# P07_BCS1_Exp_Conn.net
KiCad netlist of a schematic drawn in Altium Designer
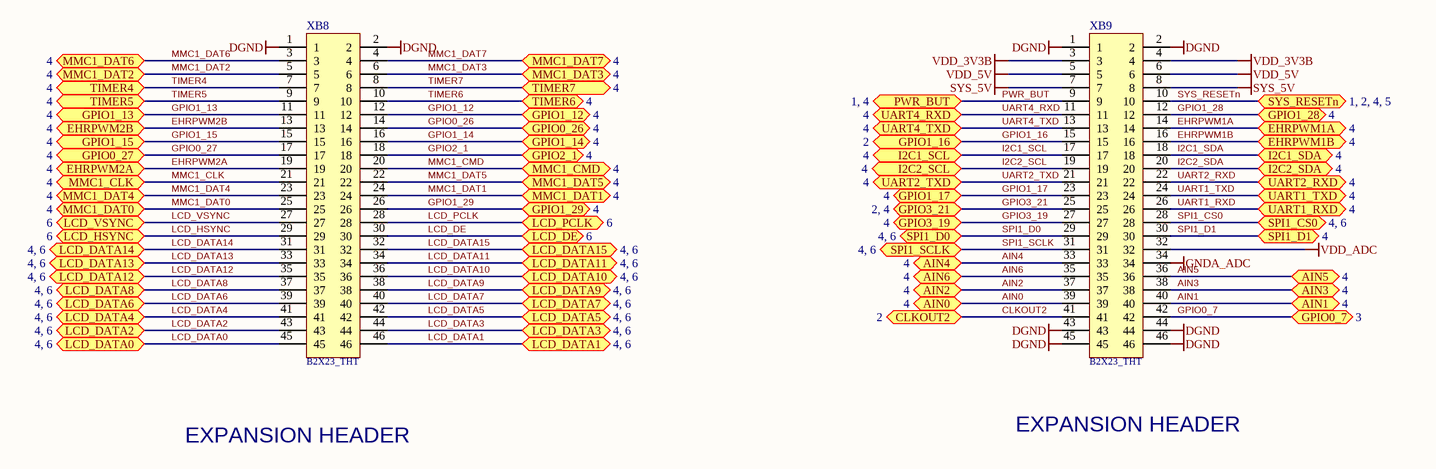
[diagram p0: P07_BCS1_Exp Conn.SchDoc]

(export (version "E")
  (design (tool "Eeschema 10.0.6"))
  (components
    (comp (ref "XB8")
      (value "B2X23_THT")
      (footprint "BU2X23")
      (description "Buchsenleiste 46pol. IDC, vertikal 2.54mm pitch")
      (libsource (lib "*") (part "XB2X23_THT"))
    )
    (comp (ref "XB9")
      (value "B2X23_THT")
      (footprint "BU2X23")
      (description "Buchsenleiste 46pol. IDC, vertikal 2.54mm pitch")
      (libsource (lib "*") (part "XB2X23_THT"))
    )
  )
  (nets
    (net (code "1") (name "/AIN0") (class "Default")
      (node (ref "XB9") (pin "39") (pinfunction "39_39") (pintype "passive"))
    )
    (net (code "2") (name "/AIN1") (class "Default")
      (node (ref "XB9") (pin "40") (pinfunction "40_40") (pintype "passive"))
    )
    (net (code "3") (name "/AIN2") (class "Default")
      (node (ref "XB9") (pin "37") (pinfunction "37_37") (pintype "passive"))
    )
    (net (code "4") (name "/AIN3") (class "Default")
      (node (ref "XB9") (pin "38") (pinfunction "38_38") (pintype "passive"))
    )
    (net (code "5") (name "/AIN4") (class "Default")
      (node (ref "XB9") (pin "33") (pinfunction "33_33") (pintype "passive"))
    )
    (net (code "6") (name "/AIN5") (class "Default")
      (node (ref "XB9") (pin "36") (pinfunction "36_36") (pintype "passive"))
    )
    (net (code "7") (name "/AIN6") (class "Default")
      (node (ref "XB9") (pin "35") (pinfunction "35_35") (pintype "passive"))
    )
    (net (code "8") (name "/CLKOUT2") (class "Default")
      (node (ref "XB9") (pin "41") (pinfunction "41_41") (pintype "passive"))
    )
    (net (code "9") (name "/EHRPWM1A") (class "Default")
      (node (ref "XB9") (pin "14") (pinfunction "14_14") (pintype "passive"))
    )
    (net (code "10") (name "/EHRPWM1B") (class "Default")
      (node (ref "XB9") (pin "16") (pinfunction "16_16") (pintype "passive"))
    )
    (net (code "11") (name "/EHRPWM2A") (class "Default")
      (node (ref "XB8") (pin "19") (pinfunction "19_19") (pintype "passive"))
    )
    (net (code "12") (name "/EHRPWM2B") (class "Default")
      (node (ref "XB8") (pin "13") (pinfunction "13_13") (pintype "passive"))
    )
    (net (code "13") (name "/GPIO0_7") (class "Default")
      (node (ref "XB9") (pin "42") (pinfunction "42_42") (pintype "passive"))
    )
    (net (code "14") (name "/GPIO0_26") (class "Default")
      (node (ref "XB8") (pin "14") (pinfunction "14_14") (pintype "passive"))
    )
    (net (code "15") (name "/GPIO0_27") (class "Default")
      (node (ref "XB8") (pin "17") (pinfunction "17_17") (pintype "passive"))
    )
    (net (code "16") (name "/GPIO1_12") (class "Default")
      (node (ref "XB8") (pin "12") (pinfunction "12_12") (pintype "passive"))
    )
    (net (code "17") (name "/GPIO1_13") (class "Default")
      (node (ref "XB8") (pin "11") (pinfunction "11_11") (pintype "passive"))
    )
    (net (code "18") (name "/GPIO1_14") (class "Default")
      (node (ref "XB8") (pin "16") (pinfunction "16_16") (pintype "passive"))
    )
    (net (code "19") (name "/GPIO1_15") (class "Default")
      (node (ref "XB8") (pin "15") (pinfunction "15_15") (pintype "passive"))
    )
    (net (code "20") (name "/GPIO1_16") (class "Default")
      (node (ref "XB9") (pin "15") (pinfunction "15_15") (pintype "passive"))
    )
    (net (code "21") (name "/GPIO1_17") (class "Default")
      (node (ref "XB9") (pin "23") (pinfunction "23_23") (pintype "passive"))
    )
    (net (code "22") (name "/GPIO1_28") (class "Default")
      (node (ref "XB9") (pin "12") (pinfunction "12_12") (pintype "passive"))
    )
    (net (code "23") (name "/GPIO1_29") (class "Default")
      (node (ref "XB8") (pin "26") (pinfunction "26_26") (pintype "passive"))
    )
    (net (code "24") (name "/GPIO2_1") (class "Default")
      (node (ref "XB8") (pin "18") (pinfunction "18_18") (pintype "passive"))
    )
    (net (code "25") (name "/GPIO3_19") (class "Default")
      (node (ref "XB9") (pin "27") (pinfunction "27_27") (pintype "passive"))
    )
    (net (code "26") (name "/GPIO3_21") (class "Default")
      (node (ref "XB9") (pin "25") (pinfunction "25_25") (pintype "passive"))
    )
    (net (code "27") (name "/I2C1_SCL") (class "Default")
      (node (ref "XB9") (pin "17") (pinfunction "17_17") (pintype "passive"))
    )
    (net (code "28") (name "/I2C1_SDA") (class "Default")
      (node (ref "XB9") (pin "18") (pinfunction "18_18") (pintype "passive"))
    )
    (net (code "29") (name "/I2C2_SCL") (class "Default")
      (node (ref "XB9") (pin "19") (pinfunction "19_19") (pintype "passive"))
    )
    (net (code "30") (name "/I2C2_SDA") (class "Default")
      (node (ref "XB9") (pin "20") (pinfunction "20_20") (pintype "passive"))
    )
    (net (code "31") (name "/LCD_DATA0") (class "Default")
      (node (ref "XB8") (pin "45") (pinfunction "45_45") (pintype "passive"))
    )
    (net (code "32") (name "/LCD_DATA1") (class "Default")
      (node (ref "XB8") (pin "46") (pinfunction "46_46") (pintype "passive"))
    )
    (net (code "33") (name "/LCD_DATA2") (class "Default")
      (node (ref "XB8") (pin "43") (pinfunction "43_43") (pintype "passive"))
    )
    (net (code "34") (name "/LCD_DATA3") (class "Default")
      (node (ref "XB8") (pin "44") (pinfunction "44_44") (pintype "passive"))
    )
    (net (code "35") (name "/LCD_DATA4") (class "Default")
      (node (ref "XB8") (pin "41") (pinfunction "41_41") (pintype "passive"))
    )
    (net (code "36") (name "/LCD_DATA5") (class "Default")
      (node (ref "XB8") (pin "42") (pinfunction "42_42") (pintype "passive"))
    )
    (net (code "37") (name "/LCD_DATA6") (class "Default")
      (node (ref "XB8") (pin "39") (pinfunction "39_39") (pintype "passive"))
    )
    (net (code "38") (name "/LCD_DATA7") (class "Default")
      (node (ref "XB8") (pin "40") (pinfunction "40_40") (pintype "passive"))
    )
    (net (code "39") (name "/LCD_DATA8") (class "Default")
      (node (ref "XB8") (pin "37") (pinfunction "37_37") (pintype "passive"))
    )
    (net (code "40") (name "/LCD_DATA9") (class "Default")
      (node (ref "XB8") (pin "38") (pinfunction "38_38") (pintype "passive"))
    )
    (net (code "41") (name "/LCD_DATA10") (class "Default")
      (node (ref "XB8") (pin "36") (pinfunction "36_36") (pintype "passive"))
    )
    (net (code "42") (name "/LCD_DATA11") (class "Default")
      (node (ref "XB8") (pin "34") (pinfunction "34_34") (pintype "passive"))
    )
    (net (code "43") (name "/LCD_DATA12") (class "Default")
      (node (ref "XB8") (pin "35") (pinfunction "35_35") (pintype "passive"))
    )
    (net (code "44") (name "/LCD_DATA13") (class "Default")
      (node (ref "XB8") (pin "33") (pinfunction "33_33") (pintype "passive"))
    )
    (net (code "45") (name "/LCD_DATA14") (class "Default")
      (node (ref "XB8") (pin "31") (pinfunction "31_31") (pintype "passive"))
    )
    (net (code "46") (name "/LCD_DATA15") (class "Default")
      (node (ref "XB8") (pin "32") (pinfunction "32_32") (pintype "passive"))
    )
    (net (code "47") (name "/LCD_DE") (class "Default")
      (node (ref "XB8") (pin "30") (pinfunction "30_30") (pintype "passive"))
    )
    (net (code "48") (name "/LCD_HSYNC") (class "Default")
      (node (ref "XB8") (pin "29") (pinfunction "29_29") (pintype "passive"))
    )
    (net (code "49") (name "/LCD_PCLK") (class "Default")
      (node (ref "XB8") (pin "28") (pinfunction "28_28") (pintype "passive"))
    )
    (net (code "50") (name "/LCD_VSYNC") (class "Default")
      (node (ref "XB8") (pin "27") (pinfunction "27_27") (pintype "passive"))
    )
    (net (code "51") (name "/MMC1_CLK") (class "Default")
      (node (ref "XB8") (pin "21") (pinfunction "21_21") (pintype "passive"))
    )
    (net (code "52") (name "/MMC1_CMD") (class "Default")
      (node (ref "XB8") (pin "20") (pinfunction "20_20") (pintype "passive"))
    )
    (net (code "53") (name "/MMC1_DAT0") (class "Default")
      (node (ref "XB8") (pin "25") (pinfunction "25_25") (pintype "passive"))
    )
    (net (code "54") (name "/MMC1_DAT1") (class "Default")
      (node (ref "XB8") (pin "24") (pinfunction "24_24") (pintype "passive"))
    )
    (net (code "55") (name "/MMC1_DAT2") (class "Default")
      (node (ref "XB8") (pin "5") (pinfunction "5_5") (pintype "passive"))
    )
    (net (code "56") (name "/MMC1_DAT3") (class "Default")
      (node (ref "XB8") (pin "6") (pinfunction "6_6") (pintype "passive"))
    )
    (net (code "57") (name "/MMC1_DAT4") (class "Default")
      (node (ref "XB8") (pin "23") (pinfunction "23_23") (pintype "passive"))
    )
    (net (code "58") (name "/MMC1_DAT5") (class "Default")
      (node (ref "XB8") (pin "22") (pinfunction "22_22") (pintype "passive"))
    )
    (net (code "59") (name "/MMC1_DAT6") (class "Default")
      (node (ref "XB8") (pin "3") (pinfunction "3_3") (pintype "passive"))
    )
    (net (code "60") (name "/MMC1_DAT7") (class "Default")
      (node (ref "XB8") (pin "4") (pinfunction "4_4") (pintype "passive"))
    )
    (net (code "61") (name "/PWR_BUT") (class "Default")
      (node (ref "XB9") (pin "9") (pinfunction "9_9") (pintype "passive"))
    )
    (net (code "62") (name "/SPI1_CS0") (class "Default")
      (node (ref "XB9") (pin "28") (pinfunction "28_28") (pintype "passive"))
    )
    (net (code "63") (name "/SPI1_D0") (class "Default")
      (node (ref "XB9") (pin "29") (pinfunction "29_29") (pintype "passive"))
    )
    (net (code "64") (name "/SPI1_D1") (class "Default")
      (node (ref "XB9") (pin "30") (pinfunction "30_30") (pintype "passive"))
    )
    (net (code "65") (name "/SPI1_SCLK") (class "Default")
      (node (ref "XB9") (pin "31") (pinfunction "31_31") (pintype "passive"))
    )
    (net (code "66") (name "/SYS_RESETn") (class "Default")
      (node (ref "XB9") (pin "10") (pinfunction "10_10") (pintype "passive"))
    )
    (net (code "67") (name "/TIMER4") (class "Default")
      (node (ref "XB8") (pin "7") (pinfunction "7_7") (pintype "passive"))
    )
    (net (code "68") (name "/TIMER5") (class "Default")
      (node (ref "XB8") (pin "9") (pinfunction "9_9") (pintype "passive"))
    )
    (net (code "69") (name "/TIMER6") (class "Default")
      (node (ref "XB8") (pin "10") (pinfunction "10_10") (pintype "passive"))
    )
    (net (code "70") (name "/TIMER7") (class "Default")
      (node (ref "XB8") (pin "8") (pinfunction "8_8") (pintype "passive"))
    )
    (net (code "71") (name "/UART1_RXD") (class "Default")
      (node (ref "XB9") (pin "26") (pinfunction "26_26") (pintype "passive"))
    )
    (net (code "72") (name "/UART1_TXD") (class "Default")
      (node (ref "XB9") (pin "24") (pinfunction "24_24") (pintype "passive"))
    )
    (net (code "73") (name "/UART2_RXD") (class "Default")
      (node (ref "XB9") (pin "22") (pinfunction "22_22") (pintype "passive"))
    )
    (net (code "74") (name "/UART2_TXD") (class "Default")
      (node (ref "XB9") (pin "21") (pinfunction "21_21") (pintype "passive"))
    )
    (net (code "75") (name "/UART4_RXD") (class "Default")
      (node (ref "XB9") (pin "11") (pinfunction "11_11") (pintype "passive"))
    )
    (net (code "76") (name "/UART4_TXD") (class "Default")
      (node (ref "XB9") (pin "13") (pinfunction "13_13") (pintype "passive"))
    )
    (net (code "77") (name "DGND") (class "Default")
      (node (ref "XB8") (pin "1") (pinfunction "1_1") (pintype "passive"))
      (node (ref "XB8") (pin "2") (pinfunction "2_2") (pintype "passive"))
      (node (ref "XB9") (pin "1") (pinfunction "1_1") (pintype "passive"))
      (node (ref "XB9") (pin "2") (pinfunction "2_2") (pintype "passive"))
      (node (ref "XB9") (pin "43") (pinfunction "43_43") (pintype "passive"))
      (node (ref "XB9") (pin "44") (pinfunction "44_44") (pintype "passive"))
      (node (ref "XB9") (pin "45") (pinfunction "45_45") (pintype "passive"))
      (node (ref "XB9") (pin "46") (pinfunction "46_46") (pintype "passive"))
    )
    (net (code "78") (name "GNDA_ADC") (class "Default")
      (node (ref "XB9") (pin "34") (pinfunction "34_34") (pintype "passive"))
    )
    (net (code "79") (name "SYS_5V") (class "Default")
      (node (ref "XB9") (pin "7") (pinfunction "7_7") (pintype "passive"))
      (node (ref "XB9") (pin "8") (pinfunction "8_8") (pintype "passive"))
    )
    (net (code "80") (name "VDD_3V3B") (class "Default")
      (node (ref "XB9") (pin "3") (pinfunction "3_3") (pintype "passive"))
      (node (ref "XB9") (pin "4") (pinfunction "4_4") (pintype "passive"))
    )
    (net (code "81") (name "VDD_5V") (class "Default")
      (node (ref "XB9") (pin "5") (pinfunction "5_5") (pintype "passive"))
      (node (ref "XB9") (pin "6") (pinfunction "6_6") (pintype "passive"))
    )
    (net (code "82") (name "VDD_ADC") (class "Default")
      (node (ref "XB9") (pin "32") (pinfunction "32_32") (pintype "passive"))
    )
  )
)
